# Encoder.net
KiCad netlist of a schematic drawn in EAGLE
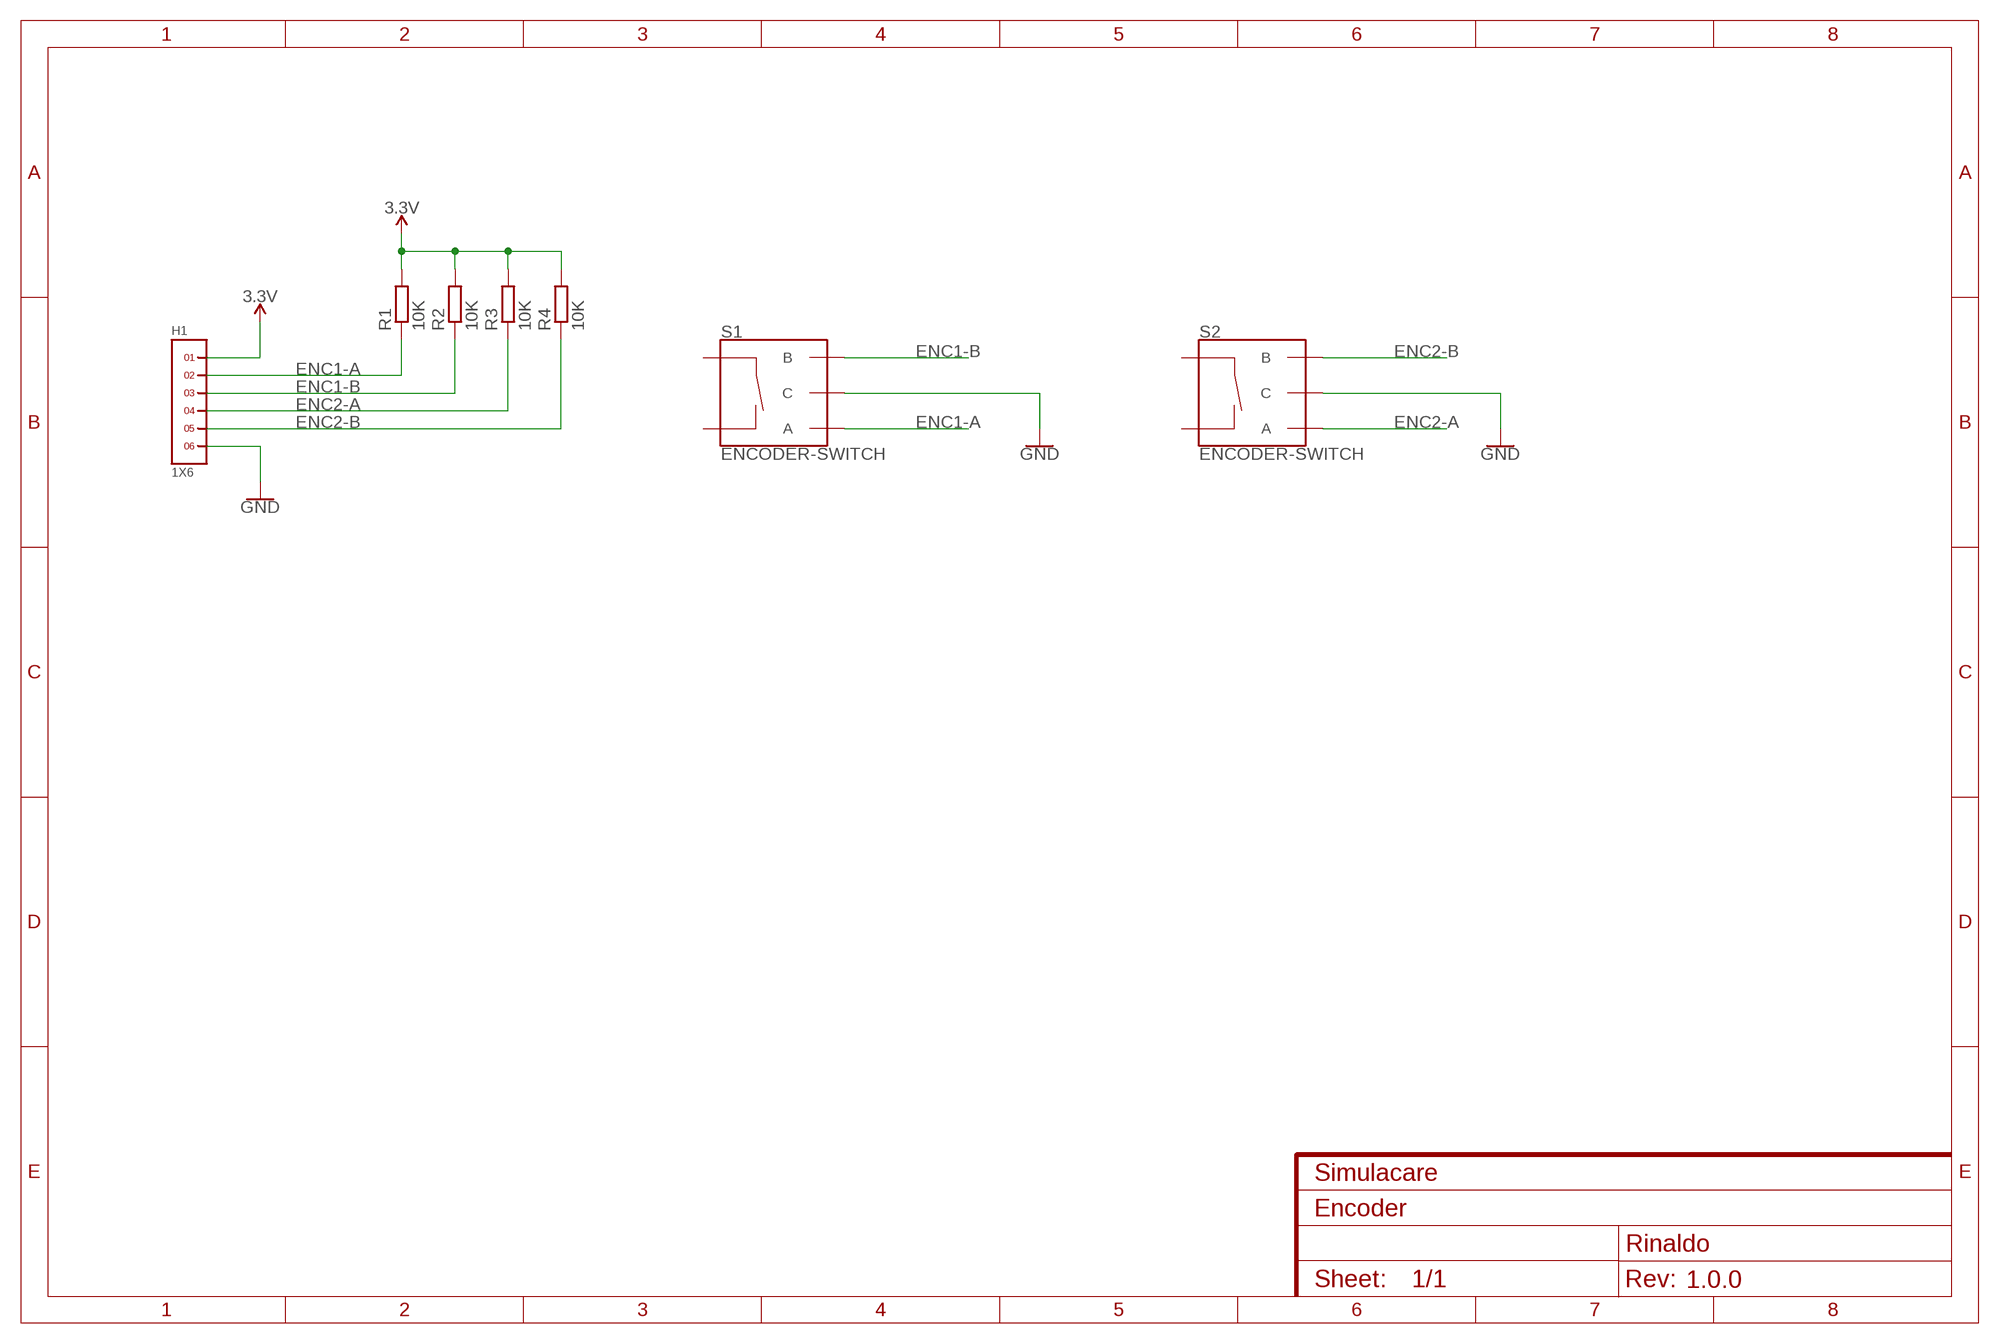
[diagram p0: schematic, sheet 1]

(export (version "E")
  (design (tool "Eeschema 10.0.6"))
  (components
    (comp (ref "H1")
      (value "1X6")
      (footprint "eagle-import:1X6")
      (libsource (lib "eagle-import") (part "1X6"))
    )
    (comp (ref "R1")
      (value "10K")
      (footprint "eagle-import:R0603")
      (libsource (lib "eagle-import") (part "R-EU_R0603"))
    )
    (comp (ref "R2")
      (value "10K")
      (footprint "eagle-import:R0603")
      (libsource (lib "eagle-import") (part "R-EU_R0603"))
    )
    (comp (ref "R3")
      (value "10K")
      (footprint "eagle-import:R0603")
      (libsource (lib "eagle-import") (part "R-EU_R0603"))
    )
    (comp (ref "R4")
      (value "10K")
      (footprint "eagle-import:R0603")
      (libsource (lib "eagle-import") (part "R-EU_R0603"))
    )
    (comp (ref "S1")
      (value "ENCODER-SWITCH")
      (footprint "eagle-import:ROTARY_ENC_PLAIN")
      (libsource (lib "eagle-import") (part "ENCODER-SWITCH"))
    )
    (comp (ref "S2")
      (value "ENCODER-SWITCH")
      (footprint "eagle-import:ROTARY_ENC_PLAIN")
      (libsource (lib "eagle-import") (part "ENCODER-SWITCH"))
    )
  )
  (nets
    (net (code "1") (name "/ENC1-A") (class "Default")
      (node (ref "H1") (pin "2") (pinfunction "2_2") (pintype "bidirectional"))
      (node (ref "R1") (pin "1") (pinfunction "1_1") (pintype "passive"))
      (node (ref "S1") (pin "A") (pinfunction "A_A") (pintype "bidirectional"))
    )
    (net (code "2") (name "/ENC1-B") (class "Default")
      (node (ref "H1") (pin "3") (pinfunction "3_3") (pintype "bidirectional"))
      (node (ref "R2") (pin "1") (pinfunction "1_1") (pintype "passive"))
      (node (ref "S1") (pin "B") (pinfunction "B_B") (pintype "bidirectional"))
    )
    (net (code "3") (name "/ENC2-A") (class "Default")
      (node (ref "H1") (pin "4") (pinfunction "4_4") (pintype "bidirectional"))
      (node (ref "R3") (pin "1") (pinfunction "1_1") (pintype "passive"))
      (node (ref "S2") (pin "A") (pinfunction "A_A") (pintype "bidirectional"))
    )
    (net (code "4") (name "/ENC2-B") (class "Default")
      (node (ref "H1") (pin "5") (pinfunction "5_5") (pintype "bidirectional"))
      (node (ref "R4") (pin "1") (pinfunction "1_1") (pintype "passive"))
      (node (ref "S2") (pin "B") (pinfunction "B_B") (pintype "bidirectional"))
    )
    (net (code "5") (name "3.3V") (class "Default")
      (node (ref "H1") (pin "1") (pinfunction "1_1") (pintype "bidirectional"))
      (node (ref "R1") (pin "2") (pinfunction "2_2") (pintype "passive"))
      (node (ref "R2") (pin "2") (pinfunction "2_2") (pintype "passive"))
      (node (ref "R3") (pin "2") (pinfunction "2_2") (pintype "passive"))
      (node (ref "R4") (pin "2") (pinfunction "2_2") (pintype "passive"))
    )
    (net (code "6") (name "GND") (class "Default")
      (node (ref "H1") (pin "6") (pinfunction "6_6") (pintype "bidirectional"))
      (node (ref "S1") (pin "C") (pinfunction "C_C") (pintype "bidirectional"))
      (node (ref "S2") (pin "C") (pinfunction "C_C") (pintype "bidirectional"))
    )
    (net (code "7") (name "unconnected-(S1-PadSW+)") (class "Default")
      (node (ref "S1") (pin "SW+") (pinfunction "SW+_SW+") (pintype "bidirectional"))
    )
    (net (code "8") (name "unconnected-(S1-PadSW-)") (class "Default")
      (node (ref "S1") (pin "SW-") (pinfunction "SW-_SW-") (pintype "bidirectional"))
    )
    (net (code "9") (name "unconnected-(S2-PadSW+)") (class "Default")
      (node (ref "S2") (pin "SW+") (pinfunction "SW+_SW+") (pintype "bidirectional"))
    )
    (net (code "10") (name "unconnected-(S2-PadSW-)") (class "Default")
      (node (ref "S2") (pin "SW-") (pinfunction "SW-_SW-") (pintype "bidirectional"))
    )
  )
)
